# PQ60_Radio_FV1.net
KiCad netlist of a schematic drawn in EAGLE
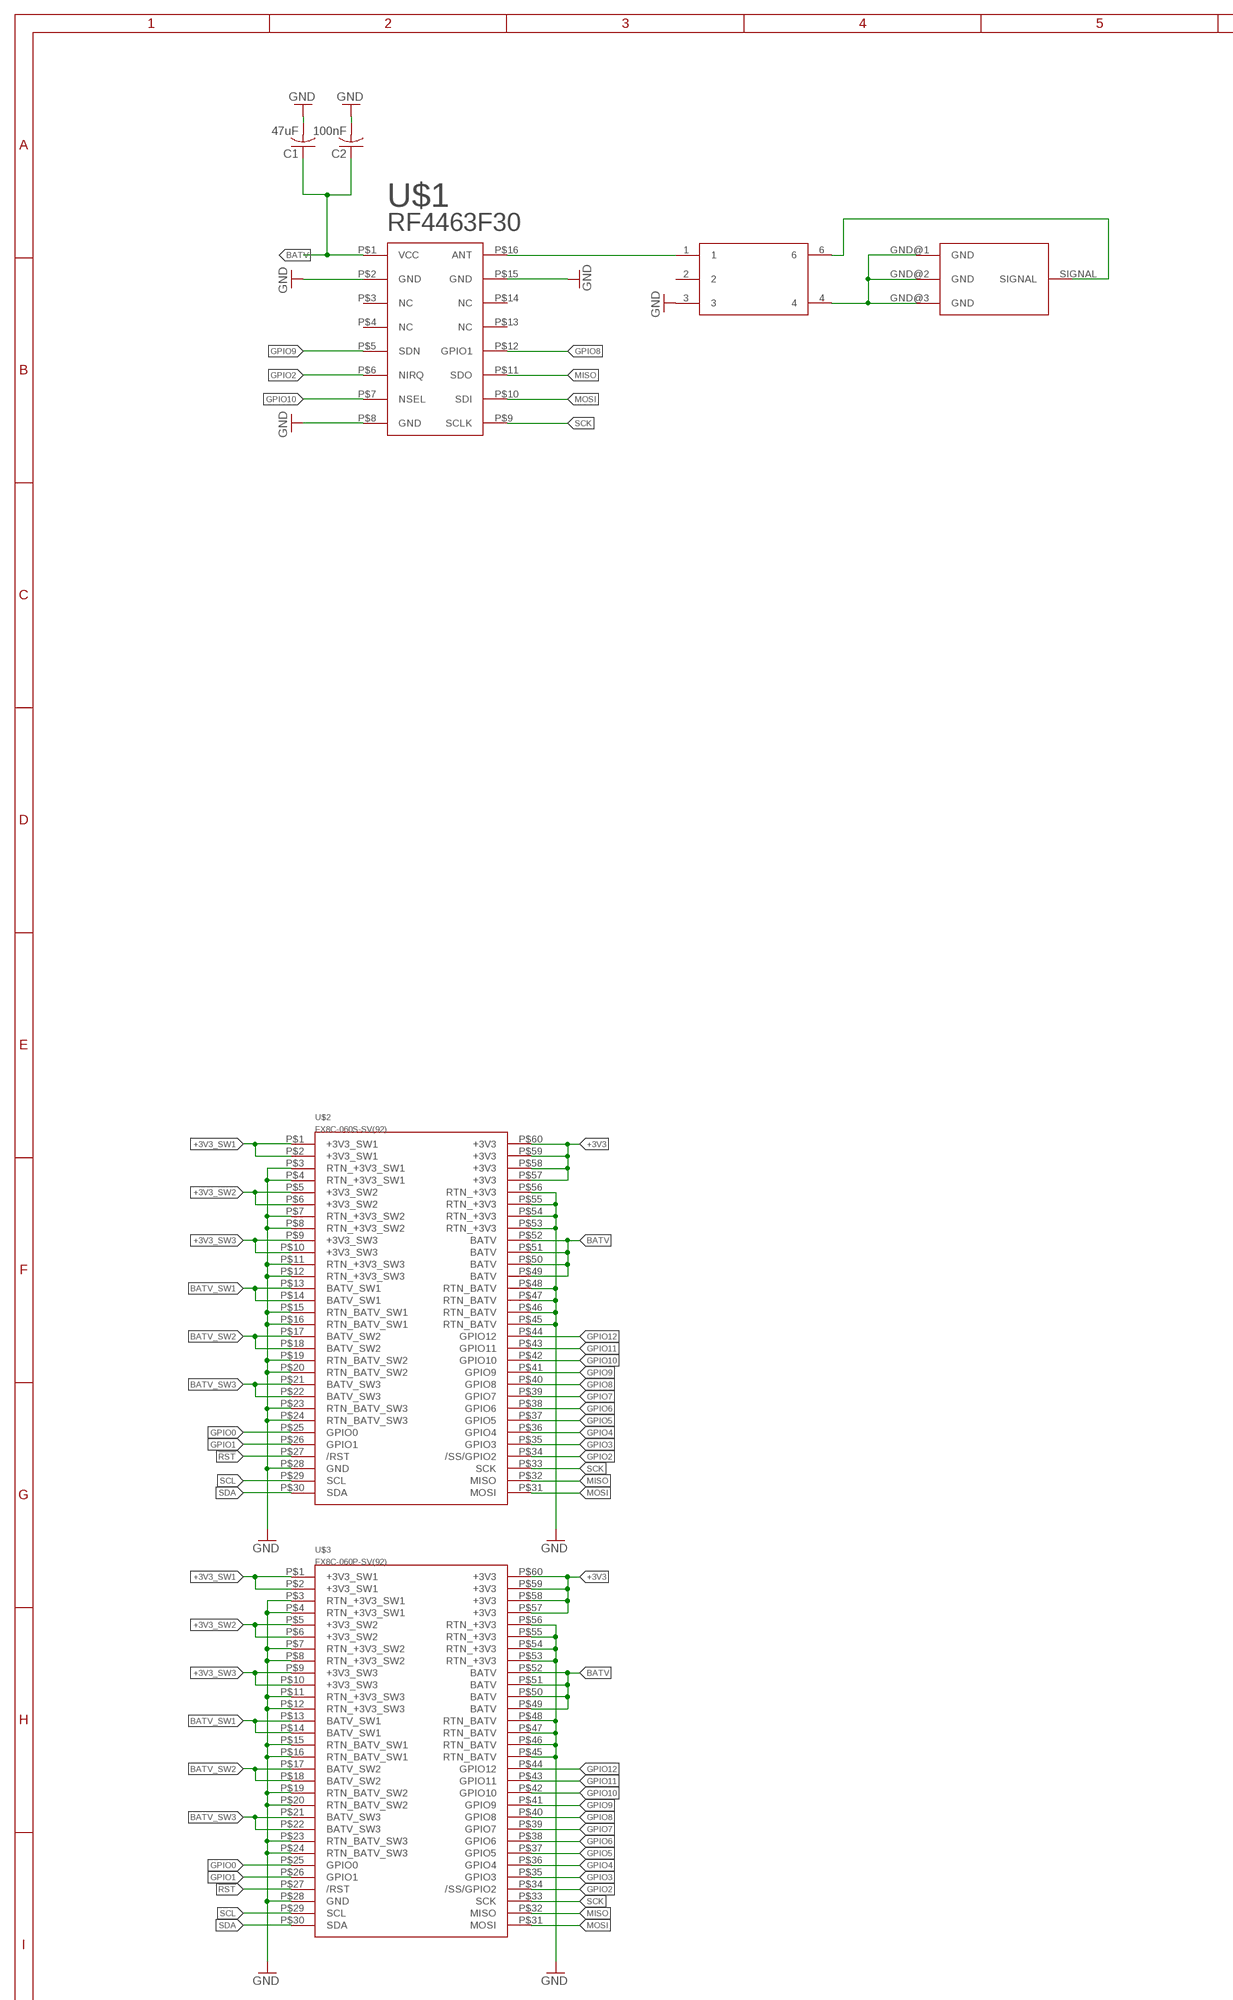
[diagram p0: schematic, sheet 1, part 1 of 2]
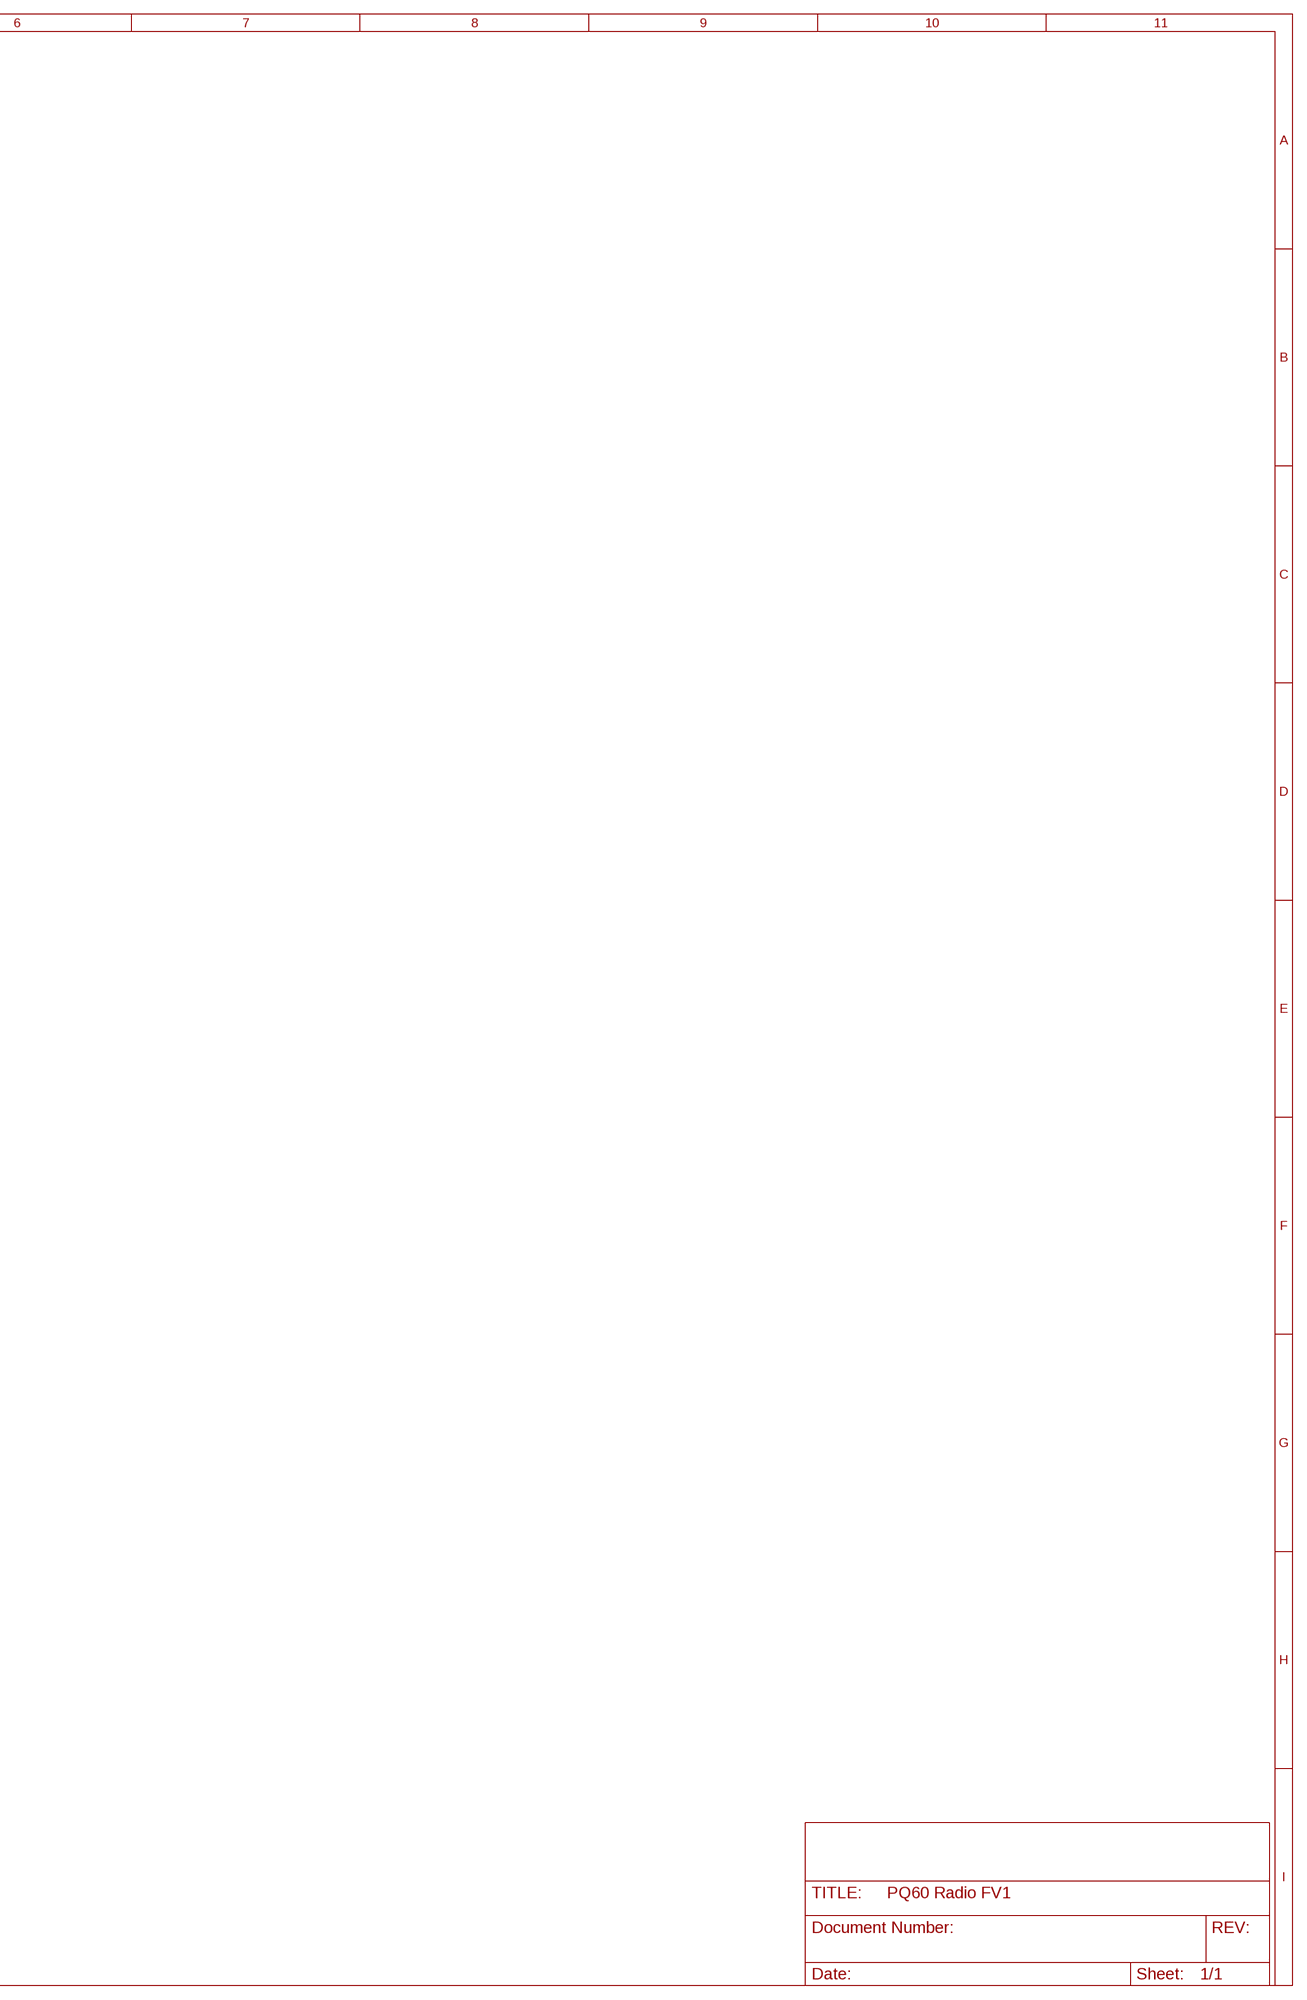
[diagram p1: schematic, sheet 1, part 2 of 2]

(export (version "E")
  (design (tool "Eeschema 10.0.6"))
  (components
    (comp (ref "C1")
      (value "47uF")
      (footprint "eagle-import:C0805")
      (libsource (lib "eagle-import") (part "C-USC0805"))
    )
    (comp (ref "C2")
      (value "100nF")
      (footprint "eagle-import:C0805")
      (libsource (lib "eagle-import") (part "C-USC0805"))
    )
    (comp (ref "CX2156NL")
      (value "CX2156NL")
      (footprint "eagle-import:CX2156NL")
      (libsource (lib "eagle-import") (part "CX2156NL"))
    )
    (comp (ref "U$1")
      (value "RF4463F30")
      (footprint "eagle-import:RF4463F30")
      (libsource (lib "eagle-import") (part "RF4463F30"))
    )
    (comp (ref "U$2")
      (value "FX8C-060S-SV(92)")
      (footprint "eagle-import:FX8C-060S-SV(92)")
      (libsource (lib "eagle-import") (part "FX8C-060S-SV(92)"))
    )
    (comp (ref "U$3")
      (value "FX8C-060P-SV(92)")
      (footprint "eagle-import:FX8C-060P-SV(92)")
      (libsource (lib "eagle-import") (part "FX8C-060P-SV(92)"))
    )
    (comp (ref "U$4")
      (value "MICRO-SMA")
      (footprint "eagle-import:MICRO-SMA")
      (libsource (lib "eagle-import") (part "MICRO-SMA"))
    )
  )
  (nets
    (net (code "1") (name "+3V3") (class "Default")
      (node (ref "U$2") (pin "P$57") (pinfunction "+3V3_P$57") (pintype "power_in"))
      (node (ref "U$2") (pin "P$58") (pinfunction "+3V3_P$58") (pintype "power_in"))
      (node (ref "U$2") (pin "P$59") (pinfunction "+3V3_P$59") (pintype "power_in"))
      (node (ref "U$2") (pin "P$60") (pinfunction "+3V3_P$60") (pintype "power_in"))
      (node (ref "U$3") (pin "P$57") (pinfunction "+3V3_P$57") (pintype "power_in"))
      (node (ref "U$3") (pin "P$58") (pinfunction "+3V3_P$58") (pintype "power_in"))
      (node (ref "U$3") (pin "P$59") (pinfunction "+3V3_P$59") (pintype "power_in"))
      (node (ref "U$3") (pin "P$60") (pinfunction "+3V3_P$60") (pintype "power_in"))
    )
    (net (code "2") (name "+3V3_SW1") (class "Default")
      (node (ref "U$2") (pin "P$1") (pinfunction "+3V3_SW1_P$1") (pintype "power_in"))
      (node (ref "U$2") (pin "P$2") (pinfunction "+3V3_SW1_P$2") (pintype "power_in"))
      (node (ref "U$3") (pin "P$1") (pinfunction "+3V3_SW1_P$1") (pintype "power_in"))
      (node (ref "U$3") (pin "P$2") (pinfunction "+3V3_SW1_P$2") (pintype "power_in"))
    )
    (net (code "3") (name "+3V3_SW2") (class "Default")
      (node (ref "U$2") (pin "P$5") (pinfunction "+3V3_SW2_P$5") (pintype "power_in"))
      (node (ref "U$2") (pin "P$6") (pinfunction "+3V3_SW2_P$6") (pintype "power_in"))
      (node (ref "U$3") (pin "P$5") (pinfunction "+3V3_SW2_P$5") (pintype "power_in"))
      (node (ref "U$3") (pin "P$6") (pinfunction "+3V3_SW2_P$6") (pintype "power_in"))
    )
    (net (code "4") (name "+3V3_SW3") (class "Default")
      (node (ref "U$2") (pin "P$10") (pinfunction "+3V3_SW3_P$10") (pintype "power_in"))
      (node (ref "U$2") (pin "P$9") (pinfunction "+3V3_SW3_P$9") (pintype "power_in"))
      (node (ref "U$3") (pin "P$10") (pinfunction "+3V3_SW3_P$10") (pintype "power_in"))
      (node (ref "U$3") (pin "P$9") (pinfunction "+3V3_SW3_P$9") (pintype "power_in"))
    )
    (net (code "5") (name "/~{RST}") (class "Default")
      (node (ref "U$2") (pin "P$27") (pinfunction "/RST_P$27") (pintype "bidirectional"))
      (node (ref "U$3") (pin "P$27") (pinfunction "/RST_P$27") (pintype "bidirectional"))
    )
    (net (code "6") (name "BATV") (class "Default")
      (node (ref "C1") (pin "1") (pinfunction "1_1") (pintype "passive"))
      (node (ref "C2") (pin "1") (pinfunction "1_1") (pintype "passive"))
      (node (ref "U$1") (pin "P$1") (pinfunction "VCC_P$1") (pintype "power_in"))
      (node (ref "U$2") (pin "P$49") (pinfunction "BATV_P$49") (pintype "power_in"))
      (node (ref "U$2") (pin "P$50") (pinfunction "BATV_P$50") (pintype "power_in"))
      (node (ref "U$2") (pin "P$51") (pinfunction "BATV_P$51") (pintype "power_in"))
      (node (ref "U$2") (pin "P$52") (pinfunction "BATV_P$52") (pintype "power_in"))
      (node (ref "U$3") (pin "P$49") (pinfunction "BATV_P$49") (pintype "power_in"))
      (node (ref "U$3") (pin "P$50") (pinfunction "BATV_P$50") (pintype "power_in"))
      (node (ref "U$3") (pin "P$51") (pinfunction "BATV_P$51") (pintype "power_in"))
      (node (ref "U$3") (pin "P$52") (pinfunction "BATV_P$52") (pintype "power_in"))
    )
    (net (code "7") (name "BATV_SW1") (class "Default")
      (node (ref "U$2") (pin "P$13") (pinfunction "BATV_SW1_P$13") (pintype "power_in"))
      (node (ref "U$2") (pin "P$14") (pinfunction "BATV_SW1_P$14") (pintype "power_in"))
      (node (ref "U$3") (pin "P$13") (pinfunction "BATV_SW1_P$13") (pintype "power_in"))
      (node (ref "U$3") (pin "P$14") (pinfunction "BATV_SW1_P$14") (pintype "power_in"))
    )
    (net (code "8") (name "BATV_SW2") (class "Default")
      (node (ref "U$2") (pin "P$17") (pinfunction "BATV_SW2_P$17") (pintype "power_in"))
      (node (ref "U$2") (pin "P$18") (pinfunction "BATV_SW2_P$18") (pintype "power_in"))
      (node (ref "U$3") (pin "P$17") (pinfunction "BATV_SW2_P$17") (pintype "power_in"))
      (node (ref "U$3") (pin "P$18") (pinfunction "BATV_SW2_P$18") (pintype "power_in"))
    )
    (net (code "9") (name "BATV_SW3") (class "Default")
      (node (ref "U$2") (pin "P$21") (pinfunction "BATV_SW3_P$21") (pintype "power_in"))
      (node (ref "U$2") (pin "P$22") (pinfunction "BATV_SW3_P$22") (pintype "power_in"))
      (node (ref "U$3") (pin "P$21") (pinfunction "BATV_SW3_P$21") (pintype "power_in"))
      (node (ref "U$3") (pin "P$22") (pinfunction "BATV_SW3_P$22") (pintype "power_in"))
    )
    (net (code "10") (name "GND") (class "Default")
      (node (ref "C1") (pin "2") (pinfunction "2_2") (pintype "passive"))
      (node (ref "C2") (pin "2") (pinfunction "2_2") (pintype "passive"))
      (node (ref "CX2156NL") (pin "3") (pinfunction "3_3") (pintype "bidirectional"))
      (node (ref "U$1") (pin "P$15") (pinfunction "GND_P$15") (pintype "power_in"))
      (node (ref "U$1") (pin "P$2") (pinfunction "GND_P$2") (pintype "power_in"))
      (node (ref "U$1") (pin "P$8") (pinfunction "GND_P$8") (pintype "power_in"))
      (node (ref "U$2") (pin "P$11") (pinfunction "RTN_+3V3_SW3_P$11") (pintype "power_in"))
      (node (ref "U$2") (pin "P$12") (pinfunction "RTN_+3V3_SW3_P$12") (pintype "power_in"))
      (node (ref "U$2") (pin "P$15") (pinfunction "RTN_BATV_SW1_P$15") (pintype "power_in"))
      (node (ref "U$2") (pin "P$16") (pinfunction "RTN_BATV_SW1_P$16") (pintype "power_in"))
      (node (ref "U$2") (pin "P$19") (pinfunction "RTN_BATV_SW2_P$19") (pintype "power_in"))
      (node (ref "U$2") (pin "P$20") (pinfunction "RTN_BATV_SW2_P$20") (pintype "power_in"))
      (node (ref "U$2") (pin "P$23") (pinfunction "RTN_BATV_SW3_P$23") (pintype "power_in"))
      (node (ref "U$2") (pin "P$24") (pinfunction "RTN_BATV_SW3_P$24") (pintype "power_in"))
      (node (ref "U$2") (pin "P$28") (pinfunction "GND_P$28") (pintype "bidirectional"))
      (node (ref "U$2") (pin "P$3") (pinfunction "RTN_+3V3_SW1_P$3") (pintype "power_in"))
      (node (ref "U$2") (pin "P$4") (pinfunction "RTN_+3V3_SW1_P$4") (pintype "power_in"))
      (node (ref "U$2") (pin "P$45") (pinfunction "RTN_BATV_P$45") (pintype "power_in"))
      (node (ref "U$2") (pin "P$46") (pinfunction "RTN_BATV_P$46") (pintype "power_in"))
      (node (ref "U$2") (pin "P$47") (pinfunction "RTN_BATV_P$47") (pintype "power_in"))
      (node (ref "U$2") (pin "P$48") (pinfunction "RTN_BATV_P$48") (pintype "power_in"))
      (node (ref "U$2") (pin "P$53") (pinfunction "RTN_+3V3_P$53") (pintype "power_in"))
      (node (ref "U$2") (pin "P$54") (pinfunction "RTN_+3V3_P$54") (pintype "power_in"))
      (node (ref "U$2") (pin "P$55") (pinfunction "RTN_+3V3_P$55") (pintype "power_in"))
      (node (ref "U$2") (pin "P$56") (pinfunction "RTN_+3V3_P$56") (pintype "power_in"))
      (node (ref "U$2") (pin "P$7") (pinfunction "RTN_+3V3_SW2_P$7") (pintype "power_in"))
      (node (ref "U$2") (pin "P$8") (pinfunction "RTN_+3V3_SW2_P$8") (pintype "power_in"))
      (node (ref "U$3") (pin "P$11") (pinfunction "RTN_+3V3_SW3_P$11") (pintype "power_in"))
      (node (ref "U$3") (pin "P$12") (pinfunction "RTN_+3V3_SW3_P$12") (pintype "power_in"))
      (node (ref "U$3") (pin "P$15") (pinfunction "RTN_BATV_SW1_P$15") (pintype "power_in"))
      (node (ref "U$3") (pin "P$16") (pinfunction "RTN_BATV_SW1_P$16") (pintype "power_in"))
      (node (ref "U$3") (pin "P$19") (pinfunction "RTN_BATV_SW2_P$19") (pintype "power_in"))
      (node (ref "U$3") (pin "P$20") (pinfunction "RTN_BATV_SW2_P$20") (pintype "power_in"))
      (node (ref "U$3") (pin "P$23") (pinfunction "RTN_BATV_SW3_P$23") (pintype "power_in"))
      (node (ref "U$3") (pin "P$24") (pinfunction "RTN_BATV_SW3_P$24") (pintype "power_in"))
      (node (ref "U$3") (pin "P$28") (pinfunction "GND_P$28") (pintype "bidirectional"))
      (node (ref "U$3") (pin "P$3") (pinfunction "RTN_+3V3_SW1_P$3") (pintype "power_in"))
      (node (ref "U$3") (pin "P$4") (pinfunction "RTN_+3V3_SW1_P$4") (pintype "power_in"))
      (node (ref "U$3") (pin "P$45") (pinfunction "RTN_BATV_P$45") (pintype "power_in"))
      (node (ref "U$3") (pin "P$46") (pinfunction "RTN_BATV_P$46") (pintype "power_in"))
      (node (ref "U$3") (pin "P$47") (pinfunction "RTN_BATV_P$47") (pintype "power_in"))
      (node (ref "U$3") (pin "P$48") (pinfunction "RTN_BATV_P$48") (pintype "power_in"))
      (node (ref "U$3") (pin "P$53") (pinfunction "RTN_+3V3_P$53") (pintype "power_in"))
      (node (ref "U$3") (pin "P$54") (pinfunction "RTN_+3V3_P$54") (pintype "power_in"))
      (node (ref "U$3") (pin "P$55") (pinfunction "RTN_+3V3_P$55") (pintype "power_in"))
      (node (ref "U$3") (pin "P$56") (pinfunction "RTN_+3V3_P$56") (pintype "power_in"))
      (node (ref "U$3") (pin "P$7") (pinfunction "RTN_+3V3_SW2_P$7") (pintype "power_in"))
      (node (ref "U$3") (pin "P$8") (pinfunction "RTN_+3V3_SW2_P$8") (pintype "power_in"))
    )
    (net (code "11") (name "GPIO0") (class "Default")
      (node (ref "U$2") (pin "P$25") (pinfunction "GPIO0_P$25") (pintype "bidirectional"))
      (node (ref "U$3") (pin "P$25") (pinfunction "GPIO0_P$25") (pintype "bidirectional"))
    )
    (net (code "12") (name "GPIO1") (class "Default")
      (node (ref "U$2") (pin "P$26") (pinfunction "GPIO1_P$26") (pintype "bidirectional"))
      (node (ref "U$3") (pin "P$26") (pinfunction "GPIO1_P$26") (pintype "bidirectional"))
    )
    (net (code "13") (name "GPIO2") (class "Default")
      (node (ref "U$1") (pin "P$6") (pinfunction "NIRQ_P$6") (pintype "bidirectional"))
      (node (ref "U$2") (pin "P$34") (pinfunction "/SS/GPIO2_P$34") (pintype "bidirectional"))
      (node (ref "U$3") (pin "P$34") (pinfunction "/SS/GPIO2_P$34") (pintype "bidirectional"))
    )
    (net (code "14") (name "GPIO3") (class "Default")
      (node (ref "U$2") (pin "P$35") (pinfunction "GPIO3_P$35") (pintype "bidirectional"))
      (node (ref "U$3") (pin "P$35") (pinfunction "GPIO3_P$35") (pintype "bidirectional"))
    )
    (net (code "15") (name "GPIO4") (class "Default")
      (node (ref "U$2") (pin "P$36") (pinfunction "GPIO4_P$36") (pintype "bidirectional"))
      (node (ref "U$3") (pin "P$36") (pinfunction "GPIO4_P$36") (pintype "bidirectional"))
    )
    (net (code "16") (name "GPIO5") (class "Default")
      (node (ref "U$2") (pin "P$37") (pinfunction "GPIO5_P$37") (pintype "bidirectional"))
      (node (ref "U$3") (pin "P$37") (pinfunction "GPIO5_P$37") (pintype "bidirectional"))
    )
    (net (code "17") (name "GPIO6") (class "Default")
      (node (ref "U$2") (pin "P$38") (pinfunction "GPIO6_P$38") (pintype "bidirectional"))
      (node (ref "U$3") (pin "P$38") (pinfunction "GPIO6_P$38") (pintype "bidirectional"))
    )
    (net (code "18") (name "GPIO7") (class "Default")
      (node (ref "U$2") (pin "P$39") (pinfunction "GPIO7_P$39") (pintype "bidirectional"))
      (node (ref "U$3") (pin "P$39") (pinfunction "GPIO7_P$39") (pintype "bidirectional"))
    )
    (net (code "19") (name "GPIO8") (class "Default")
      (node (ref "U$1") (pin "P$12") (pinfunction "GPIO1_P$12") (pintype "bidirectional"))
      (node (ref "U$2") (pin "P$40") (pinfunction "GPIO8_P$40") (pintype "bidirectional"))
      (node (ref "U$3") (pin "P$40") (pinfunction "GPIO8_P$40") (pintype "bidirectional"))
    )
    (net (code "20") (name "GPIO9") (class "Default")
      (node (ref "U$1") (pin "P$5") (pinfunction "SDN_P$5") (pintype "bidirectional"))
      (node (ref "U$2") (pin "P$41") (pinfunction "GPIO9_P$41") (pintype "bidirectional"))
      (node (ref "U$3") (pin "P$41") (pinfunction "GPIO9_P$41") (pintype "bidirectional"))
    )
    (net (code "21") (name "GPIO10") (class "Default")
      (node (ref "U$1") (pin "P$7") (pinfunction "NSEL_P$7") (pintype "bidirectional"))
      (node (ref "U$2") (pin "P$42") (pinfunction "GPIO10_P$42") (pintype "bidirectional"))
      (node (ref "U$3") (pin "P$42") (pinfunction "GPIO10_P$42") (pintype "bidirectional"))
    )
    (net (code "22") (name "GPIO11") (class "Default")
      (node (ref "U$2") (pin "P$43") (pinfunction "GPIO11_P$43") (pintype "bidirectional"))
      (node (ref "U$3") (pin "P$43") (pinfunction "GPIO11_P$43") (pintype "bidirectional"))
    )
    (net (code "23") (name "GPIO12") (class "Default")
      (node (ref "U$2") (pin "P$44") (pinfunction "GPIO12_P$44") (pintype "bidirectional"))
      (node (ref "U$3") (pin "P$44") (pinfunction "GPIO12_P$44") (pintype "bidirectional"))
    )
    (net (code "24") (name "MISO") (class "Default")
      (node (ref "U$1") (pin "P$11") (pinfunction "SDO_P$11") (pintype "bidirectional"))
      (node (ref "U$2") (pin "P$32") (pinfunction "MISO_P$32") (pintype "bidirectional"))
      (node (ref "U$3") (pin "P$32") (pinfunction "MISO_P$32") (pintype "bidirectional"))
    )
    (net (code "25") (name "MOSI") (class "Default")
      (node (ref "U$1") (pin "P$10") (pinfunction "SDI_P$10") (pintype "bidirectional"))
      (node (ref "U$2") (pin "P$31") (pinfunction "MOSI_P$31") (pintype "bidirectional"))
      (node (ref "U$3") (pin "P$31") (pinfunction "MOSI_P$31") (pintype "bidirectional"))
    )
    (net (code "26") (name "Net-(CX2156NL-Pad4)") (class "Default")
      (node (ref "CX2156NL") (pin "4") (pinfunction "4_4") (pintype "bidirectional"))
      (node (ref "U$4") (pin "GND@1") (pinfunction "GND_GND@1") (pintype "bidirectional"))
      (node (ref "U$4") (pin "GND@2") (pinfunction "GND_GND@2") (pintype "bidirectional"))
      (node (ref "U$4") (pin "GND@3") (pinfunction "GND_GND@3") (pintype "bidirectional"))
    )
    (net (code "27") (name "Net-(CX2156NL-Pad6)") (class "Default")
      (node (ref "CX2156NL") (pin "6") (pinfunction "6_6") (pintype "bidirectional"))
      (node (ref "U$4") (pin "SIGNAL") (pinfunction "SIGNAL_SIGNAL") (pintype "bidirectional"))
    )
    (net (code "28") (name "Net-(U$1-ANT)") (class "Default")
      (node (ref "CX2156NL") (pin "1") (pinfunction "1_1") (pintype "bidirectional"))
      (node (ref "U$1") (pin "P$16") (pinfunction "ANT_P$16") (pintype "bidirectional"))
    )
    (net (code "29") (name "SCK") (class "Default")
      (node (ref "U$1") (pin "P$9") (pinfunction "SCLK_P$9") (pintype "bidirectional"))
      (node (ref "U$2") (pin "P$33") (pinfunction "SCK_P$33") (pintype "bidirectional"))
      (node (ref "U$3") (pin "P$33") (pinfunction "SCK_P$33") (pintype "bidirectional"))
    )
    (net (code "30") (name "SCL") (class "Default")
      (node (ref "U$2") (pin "P$29") (pinfunction "SCL_P$29") (pintype "bidirectional"))
      (node (ref "U$3") (pin "P$29") (pinfunction "SCL_P$29") (pintype "bidirectional"))
    )
    (net (code "31") (name "SDA") (class "Default")
      (node (ref "U$2") (pin "P$30") (pinfunction "SDA_P$30") (pintype "bidirectional"))
      (node (ref "U$3") (pin "P$30") (pinfunction "SDA_P$30") (pintype "bidirectional"))
    )
    (net (code "32") (name "unconnected-(CX2156NL-Pad2)") (class "Default")
      (node (ref "CX2156NL") (pin "2") (pinfunction "2_2") (pintype "bidirectional"))
    )
    (net (code "33") (name "unconnected-(U$1-NC-PadP$3)") (class "Default")
      (node (ref "U$1") (pin "P$3") (pinfunction "NC_P$3") (pintype "no_connect"))
    )
    (net (code "34") (name "unconnected-(U$1-NC-PadP$4)") (class "Default")
      (node (ref "U$1") (pin "P$4") (pinfunction "NC_P$4") (pintype "no_connect"))
    )
    (net (code "35") (name "unconnected-(U$1-NC-PadP$13)") (class "Default")
      (node (ref "U$1") (pin "P$13") (pinfunction "NC_P$13") (pintype "no_connect"))
    )
    (net (code "36") (name "unconnected-(U$1-NC-PadP$14)") (class "Default")
      (node (ref "U$1") (pin "P$14") (pinfunction "NC_P$14") (pintype "no_connect"))
    )
  )
)
